# COMECA_TestSCH.net
KiCad netlist of a schematic drawn in Altium Designer
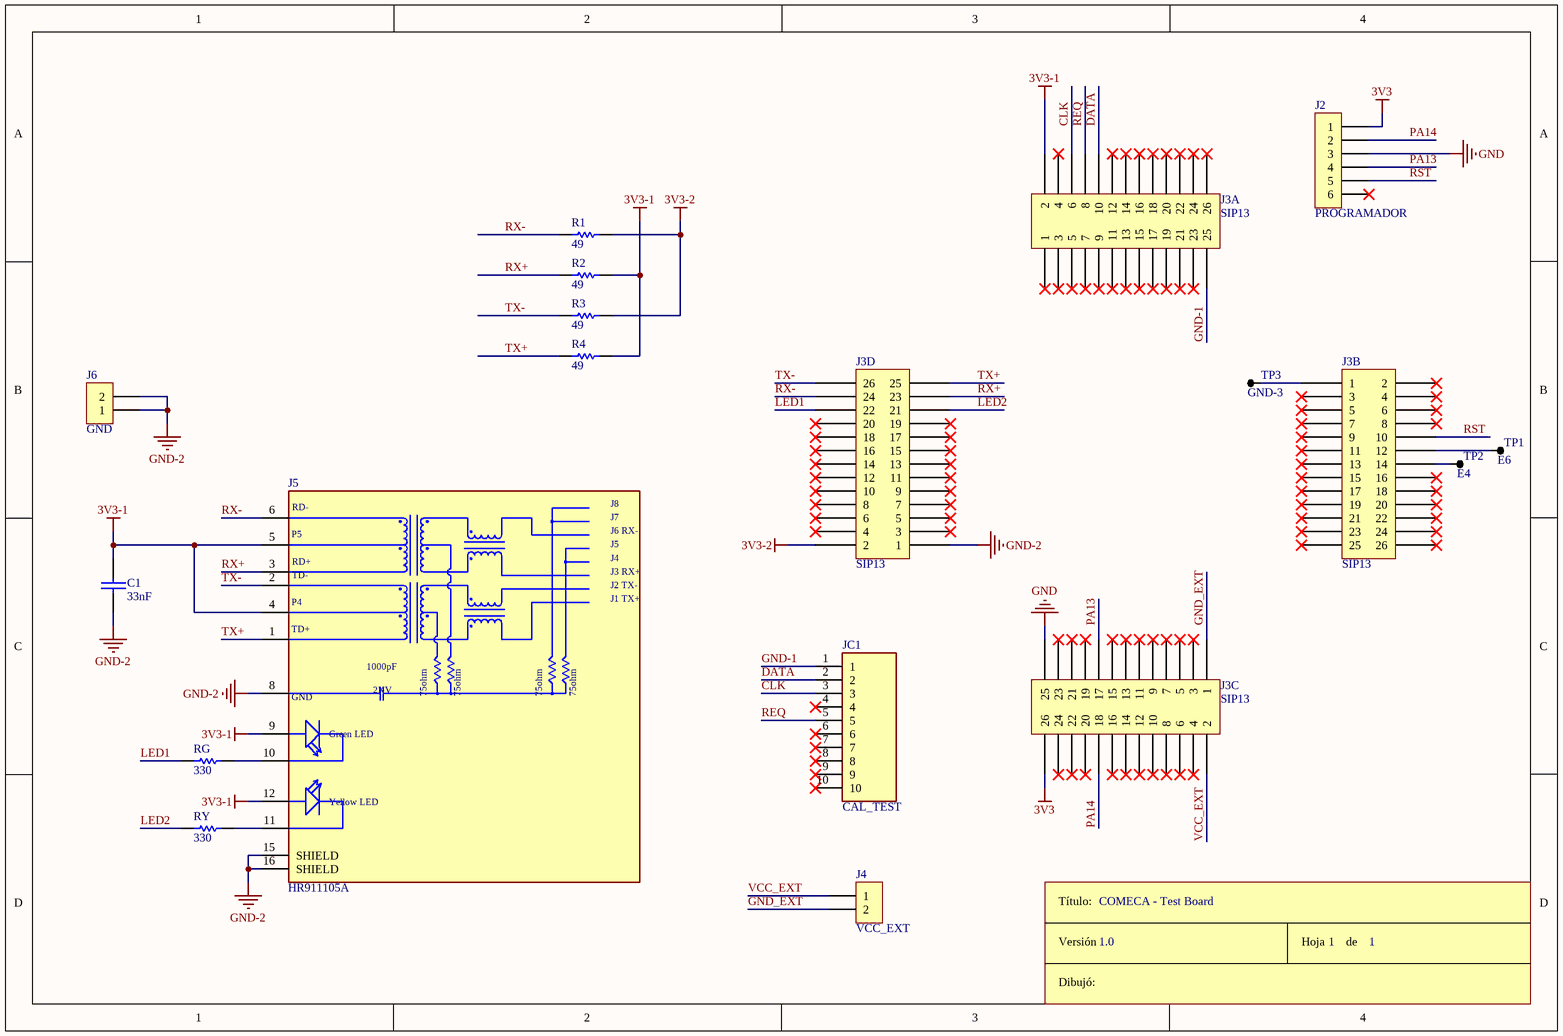
[diagram p0: COMECA_TestSCH.SchDoc]

(export (version "E")
  (design (tool "Eeschema 10.0.6"))
  (components
    (comp (ref "C1") (value "33nF") (footprint "CAP100") (libsource (lib "LIBEBAL") (part "CAP")))
    (comp (ref "J2") (value "PROGRAMADOR") (footprint "SIP6") (libsource (lib "LIBEBAL") (part "CON6")))
    (comp (ref "J3A")
      (value "SIP13")
      (footprint "SIP13*2 - HDR")
      (libsource (lib "AditionalComponents") (part "CON13*2"))
    )
    (comp (ref "J3B") (value "SIP13") (footprint "SIP13*2 - HDR") (libsource (lib "") (part "CON13*2_2")))
    (comp (ref "J3C") (value "SIP13") (footprint "SIP13*2 - HDR") (libsource (lib "") (part "CON13*2_1")))
    (comp (ref "J3D") (value "SIP13") (footprint "SIP13*2 - HDR") (libsource (lib "") (part "CON13*2_3")))
    (comp (ref "J4") (value "VCC_EXT") (footprint "SIP2") (libsource (lib "") (part "CON2_1")))
    (comp (ref "J5")
      (value "HR911105A")
      (footprint "HANRUN_HR911105A")
      (description "HR911105A Ethernet Interface Arduino Platform Evaluation Expansion Board")
      (fields (field (name "MF") "DFRobot"))
      (libsource (lib "HR911105A") (part "HR911105A"))
    )
    (comp (ref "J6") (value "GND") (footprint "SIP2") (libsource (lib "LIBEBAL") (part "CON2")))
    (comp (ref "JC1")
      (value "CAL_TEST")
      (footprint "TE_5104338-1 - 90DEG")
      (description "HEADER; PIN; AMP-LATCH; 10 POS; 2.54 X 2.54; VERTICAL; LOW PROFILE; PCB")
      (fields (field (name "MF") "TE Connectivity") (field (name "MP") "5104338-1"))
      (libsource (lib "HDR10-M") (part "5104338-1"))
    )
    (comp (ref "R1") (value "49") (footprint "RES400") (libsource (lib "LIBEBAL") (part "RES")))
    (comp (ref "R2") (value "49") (footprint "RES400") (libsource (lib "LIBEBAL") (part "RES")))
    (comp (ref "R3") (value "49") (footprint "RES400") (libsource (lib "LIBEBAL") (part "RES")))
    (comp (ref "R4") (value "49") (footprint "RES400") (libsource (lib "LIBEBAL") (part "RES")))
    (comp (ref "RG") (value "330") (footprint "RES400") (libsource (lib "LIBEBAL") (part "RES")))
    (comp (ref "ROT1") (value "Rótulo") (libsource (lib "LIB PIO IX") (part "Rótulo")))
    (comp (ref "RY") (value "330") (footprint "RES400") (libsource (lib "LIBEBAL") (part "RES")))
    (comp (ref "TP1") (value "E6") (footprint "TPTH") (libsource (lib "LIBEBAL") (part "TP")))
    (comp (ref "TP2") (value "E4") (footprint "TPTH") (libsource (lib "LIBEBAL") (part "TP")))
    (comp (ref "TP3") (value "GND-3") (footprint "TPTH") (libsource (lib "LIBEBAL") (part "TP")))
  )
  (nets
    (net (code "1") (name "/CLK") (class "Default")
      (node (ref "J3A") (pin "6") (pinfunction "6_6") (pintype "passive"))
      (node (ref "JC1") (pin "3") (pinfunction "3_3") (pintype "passive"))
    )
    (net (code "2") (name "/DATA") (class "Default")
      (node (ref "J3A") (pin "10") (pinfunction "10_10") (pintype "passive"))
      (node (ref "JC1") (pin "2") (pinfunction "2_2") (pintype "passive"))
    )
    (net (code "3") (name "/GND-1") (class "Default")
      (node (ref "J3A") (pin "25") (pinfunction "25_25") (pintype "passive"))
      (node (ref "JC1") (pin "1") (pinfunction "1_1") (pintype "passive"))
    )
    (net (code "4") (name "/GND_EXT") (class "Default")
      (node (ref "J3C") (pin "1") (pinfunction "1_1") (pintype "passive"))
      (node (ref "J4") (pin "2") (pinfunction "2_2") (pintype "passive"))
    )
    (net (code "5") (name "/LED1") (class "Default")
      (node (ref "J3D") (pin "22") (pinfunction "22_22") (pintype "passive"))
      (node (ref "RG") (pin "1") (pinfunction "1_1") (pintype "passive"))
    )
    (net (code "6") (name "/LED2") (class "Default")
      (node (ref "J3D") (pin "21") (pinfunction "21_21") (pintype "passive"))
      (node (ref "RY") (pin "1") (pinfunction "1_1") (pintype "passive"))
    )
    (net (code "7") (name "/PA13") (class "Default")
      (node (ref "J2") (pin "4") (pinfunction "4_4") (pintype "passive"))
      (node (ref "J3C") (pin "17") (pinfunction "17_17") (pintype "passive"))
    )
    (net (code "8") (name "/PA14") (class "Default")
      (node (ref "J2") (pin "2") (pinfunction "2_2") (pintype "passive"))
      (node (ref "J3C") (pin "18") (pinfunction "18_18") (pintype "passive"))
    )
    (net (code "9") (name "/REQ") (class "Default")
      (node (ref "J3A") (pin "8") (pinfunction "8_8") (pintype "passive"))
      (node (ref "JC1") (pin "5") (pinfunction "5_5") (pintype "passive"))
    )
    (net (code "10") (name "/RST") (class "Default")
      (node (ref "J2") (pin "5") (pinfunction "5_5") (pintype "passive"))
      (node (ref "J3B") (pin "10") (pinfunction "10_10") (pintype "passive"))
    )
    (net (code "11") (name "/RX+") (class "Default")
      (node (ref "J3D") (pin "23") (pinfunction "23_23") (pintype "passive"))
      (node (ref "J5") (pin "3") (pinfunction "RD+_3") (pintype "passive"))
      (node (ref "R2") (pin "1") (pinfunction "1_1") (pintype "passive"))
    )
    (net (code "12") (name "/RX-") (class "Default")
      (node (ref "J3D") (pin "24") (pinfunction "24_24") (pintype "passive"))
      (node (ref "J5") (pin "6") (pinfunction "RD-_6") (pintype "passive"))
      (node (ref "R1") (pin "1") (pinfunction "1_1") (pintype "passive"))
    )
    (net (code "13") (name "/TX+") (class "Default")
      (node (ref "J3D") (pin "25") (pinfunction "25_25") (pintype "passive"))
      (node (ref "J5") (pin "1") (pinfunction "TD+_1") (pintype "passive"))
      (node (ref "R4") (pin "1") (pinfunction "1_1") (pintype "passive"))
    )
    (net (code "14") (name "/TX-") (class "Default")
      (node (ref "J3D") (pin "26") (pinfunction "26_26") (pintype "passive"))
      (node (ref "J5") (pin "2") (pinfunction "TD-_2") (pintype "passive"))
      (node (ref "R3") (pin "1") (pinfunction "1_1") (pintype "passive"))
    )
    (net (code "15") (name "/VCC_EXT") (class "Default")
      (node (ref "J3C") (pin "2") (pinfunction "2_2") (pintype "passive"))
      (node (ref "J4") (pin "1") (pinfunction "1_1") (pintype "passive"))
    )
    (net (code "16") (name "3V3") (class "Default")
      (node (ref "J2") (pin "1") (pinfunction "1_1") (pintype "passive"))
      (node (ref "J3C") (pin "26") (pinfunction "26_26") (pintype "passive"))
    )
    (net (code "17") (name "3V3-1") (class "Default")
      (node (ref "C1") (pin "1") (pinfunction "1_1") (pintype "passive"))
      (node (ref "J3A") (pin "2") (pinfunction "2_2") (pintype "passive"))
      (node (ref "J5") (pin "12") (pinfunction "YA_12") (pintype "passive"))
      (node (ref "J5") (pin "4") (pinfunction "P4_4") (pintype "passive"))
      (node (ref "J5") (pin "5") (pinfunction "P5_5") (pintype "passive"))
      (node (ref "J5") (pin "9") (pinfunction "GA_9") (pintype "passive"))
      (node (ref "R2") (pin "2") (pinfunction "2_2") (pintype "passive"))
      (node (ref "R4") (pin "2") (pinfunction "2_2") (pintype "passive"))
    )
    (net (code "18") (name "3V3-2") (class "Default")
      (node (ref "J3D") (pin "2") (pinfunction "2_2") (pintype "passive"))
      (node (ref "R1") (pin "2") (pinfunction "2_2") (pintype "passive"))
      (node (ref "R3") (pin "2") (pinfunction "2_2") (pintype "passive"))
    )
    (net (code "19") (name "GND") (class "Default")
      (node (ref "J2") (pin "3") (pinfunction "3_3") (pintype "passive"))
      (node (ref "J3C") (pin "25") (pinfunction "25_25") (pintype "passive"))
    )
    (net (code "20") (name "GND-2") (class "Default")
      (node (ref "C1") (pin "2") (pinfunction "2_2") (pintype "passive"))
      (node (ref "J3D") (pin "1") (pinfunction "1_1") (pintype "passive"))
      (node (ref "J5") (pin "15") (pinfunction "SHIELD_15") (pintype "passive"))
      (node (ref "J5") (pin "16") (pinfunction "SHIELD_16") (pintype "passive"))
      (node (ref "J5") (pin "8") (pinfunction "GND_8") (pintype "power_in"))
      (node (ref "J6") (pin "1") (pinfunction "1_1") (pintype "passive"))
      (node (ref "J6") (pin "2") (pinfunction "2_2") (pintype "passive"))
    )
    (net (code "21") (name "Net-(J3B-Pad1)") (class "Default")
      (node (ref "J3B") (pin "1") (pinfunction "1_1") (pintype "passive"))
      (node (ref "TP3") (pin "1") (pinfunction "1_1") (pintype "passive"))
    )
    (net (code "22") (name "Net-(J3B-Pad12)") (class "Default")
      (node (ref "J3B") (pin "12") (pinfunction "12_12") (pintype "passive"))
      (node (ref "TP1") (pin "1") (pinfunction "1_1") (pintype "passive"))
    )
    (net (code "23") (name "Net-(J3B-Pad14)") (class "Default")
      (node (ref "J3B") (pin "14") (pinfunction "14_14") (pintype "passive"))
      (node (ref "TP2") (pin "1") (pinfunction "1_1") (pintype "passive"))
    )
    (net (code "24") (name "Net-(J5-GC)") (class "Default")
      (node (ref "J5") (pin "10") (pinfunction "GC_10") (pintype "passive"))
      (node (ref "RG") (pin "2") (pinfunction "2_2") (pintype "passive"))
    )
    (net (code "25") (name "Net-(J5-YC)") (class "Default")
      (node (ref "J5") (pin "11") (pinfunction "YC_11") (pintype "passive"))
      (node (ref "RY") (pin "2") (pinfunction "2_2") (pintype "passive"))
    )
    (net (code "26") (name "unconnected-(J2-Pad6)") (class "Default")
      (node (ref "J2") (pin "6") (pinfunction "6_6") (pintype "passive+no_connect"))
    )
    (net (code "27") (name "unconnected-(J3A-Pad1)") (class "Default")
      (node (ref "J3A") (pin "1") (pinfunction "1_1") (pintype "passive+no_connect"))
    )
    (net (code "28") (name "unconnected-(J3A-Pad3)") (class "Default")
      (node (ref "J3A") (pin "3") (pinfunction "3_3") (pintype "passive+no_connect"))
    )
    (net (code "29") (name "unconnected-(J3A-Pad4)") (class "Default")
      (node (ref "J3A") (pin "4") (pinfunction "4_4") (pintype "passive+no_connect"))
    )
    (net (code "30") (name "unconnected-(J3A-Pad5)") (class "Default")
      (node (ref "J3A") (pin "5") (pinfunction "5_5") (pintype "passive+no_connect"))
    )
    (net (code "31") (name "unconnected-(J3A-Pad7)") (class "Default")
      (node (ref "J3A") (pin "7") (pinfunction "7_7") (pintype "passive+no_connect"))
    )
    (net (code "32") (name "unconnected-(J3A-Pad9)") (class "Default")
      (node (ref "J3A") (pin "9") (pinfunction "9_9") (pintype "passive+no_connect"))
    )
    (net (code "33") (name "unconnected-(J3A-Pad11)") (class "Default")
      (node (ref "J3A") (pin "11") (pinfunction "11_11") (pintype "passive+no_connect"))
    )
    (net (code "34") (name "unconnected-(J3A-Pad12)") (class "Default")
      (node (ref "J3A") (pin "12") (pinfunction "12_12") (pintype "passive+no_connect"))
    )
    (net (code "35") (name "unconnected-(J3A-Pad13)") (class "Default")
      (node (ref "J3A") (pin "13") (pinfunction "13_13") (pintype "passive+no_connect"))
    )
    (net (code "36") (name "unconnected-(J3A-Pad14)") (class "Default")
      (node (ref "J3A") (pin "14") (pinfunction "14_14") (pintype "passive+no_connect"))
    )
    (net (code "37") (name "unconnected-(J3A-Pad15)") (class "Default")
      (node (ref "J3A") (pin "15") (pinfunction "15_15") (pintype "passive+no_connect"))
    )
    (net (code "38") (name "unconnected-(J3A-Pad16)") (class "Default")
      (node (ref "J3A") (pin "16") (pinfunction "16_16") (pintype "passive+no_connect"))
    )
    (net (code "39") (name "unconnected-(J3A-Pad17)") (class "Default")
      (node (ref "J3A") (pin "17") (pinfunction "17_17") (pintype "passive+no_connect"))
    )
    (net (code "40") (name "unconnected-(J3A-Pad18)") (class "Default")
      (node (ref "J3A") (pin "18") (pinfunction "18_18") (pintype "passive+no_connect"))
    )
    (net (code "41") (name "unconnected-(J3A-Pad19)") (class "Default")
      (node (ref "J3A") (pin "19") (pinfunction "19_19") (pintype "passive+no_connect"))
    )
    (net (code "42") (name "unconnected-(J3A-Pad20)") (class "Default")
      (node (ref "J3A") (pin "20") (pinfunction "20_20") (pintype "passive+no_connect"))
    )
    (net (code "43") (name "unconnected-(J3A-Pad21)") (class "Default")
      (node (ref "J3A") (pin "21") (pinfunction "21_21") (pintype "passive+no_connect"))
    )
    (net (code "44") (name "unconnected-(J3A-Pad22)") (class "Default")
      (node (ref "J3A") (pin "22") (pinfunction "22_22") (pintype "passive+no_connect"))
    )
    (net (code "45") (name "unconnected-(J3A-Pad23)") (class "Default")
      (node (ref "J3A") (pin "23") (pinfunction "23_23") (pintype "passive+no_connect"))
    )
    (net (code "46") (name "unconnected-(J3A-Pad24)") (class "Default")
      (node (ref "J3A") (pin "24") (pinfunction "24_24") (pintype "passive+no_connect"))
    )
    (net (code "47") (name "unconnected-(J3A-Pad26)") (class "Default")
      (node (ref "J3A") (pin "26") (pinfunction "26_26") (pintype "passive+no_connect"))
    )
    (net (code "48") (name "unconnected-(J3B-Pad2)") (class "Default")
      (node (ref "J3B") (pin "2") (pinfunction "2_2") (pintype "passive+no_connect"))
    )
    (net (code "49") (name "unconnected-(J3B-Pad3)") (class "Default")
      (node (ref "J3B") (pin "3") (pinfunction "3_3") (pintype "passive+no_connect"))
    )
    (net (code "50") (name "unconnected-(J3B-Pad4)") (class "Default")
      (node (ref "J3B") (pin "4") (pinfunction "4_4") (pintype "passive+no_connect"))
    )
    (net (code "51") (name "unconnected-(J3B-Pad5)") (class "Default")
      (node (ref "J3B") (pin "5") (pinfunction "5_5") (pintype "passive+no_connect"))
    )
    (net (code "52") (name "unconnected-(J3B-Pad6)") (class "Default")
      (node (ref "J3B") (pin "6") (pinfunction "6_6") (pintype "passive+no_connect"))
    )
    (net (code "53") (name "unconnected-(J3B-Pad7)") (class "Default")
      (node (ref "J3B") (pin "7") (pinfunction "7_7") (pintype "passive+no_connect"))
    )
    (net (code "54") (name "unconnected-(J3B-Pad8)") (class "Default")
      (node (ref "J3B") (pin "8") (pinfunction "8_8") (pintype "passive+no_connect"))
    )
    (net (code "55") (name "unconnected-(J3B-Pad9)") (class "Default")
      (node (ref "J3B") (pin "9") (pinfunction "9_9") (pintype "passive+no_connect"))
    )
    (net (code "56") (name "unconnected-(J3B-Pad11)") (class "Default")
      (node (ref "J3B") (pin "11") (pinfunction "11_11") (pintype "passive+no_connect"))
    )
    (net (code "57") (name "unconnected-(J3B-Pad13)") (class "Default")
      (node (ref "J3B") (pin "13") (pinfunction "13_13") (pintype "passive+no_connect"))
    )
    (net (code "58") (name "unconnected-(J3B-Pad15)") (class "Default")
      (node (ref "J3B") (pin "15") (pinfunction "15_15") (pintype "passive+no_connect"))
    )
    (net (code "59") (name "unconnected-(J3B-Pad16)") (class "Default")
      (node (ref "J3B") (pin "16") (pinfunction "16_16") (pintype "passive+no_connect"))
    )
    (net (code "60") (name "unconnected-(J3B-Pad17)") (class "Default")
      (node (ref "J3B") (pin "17") (pinfunction "17_17") (pintype "passive+no_connect"))
    )
    (net (code "61") (name "unconnected-(J3B-Pad18)") (class "Default")
      (node (ref "J3B") (pin "18") (pinfunction "18_18") (pintype "passive+no_connect"))
    )
    (net (code "62") (name "unconnected-(J3B-Pad19)") (class "Default")
      (node (ref "J3B") (pin "19") (pinfunction "19_19") (pintype "passive+no_connect"))
    )
    (net (code "63") (name "unconnected-(J3B-Pad20)") (class "Default")
      (node (ref "J3B") (pin "20") (pinfunction "20_20") (pintype "passive+no_connect"))
    )
    (net (code "64") (name "unconnected-(J3B-Pad21)") (class "Default")
      (node (ref "J3B") (pin "21") (pinfunction "21_21") (pintype "passive+no_connect"))
    )
    (net (code "65") (name "unconnected-(J3B-Pad22)") (class "Default")
      (node (ref "J3B") (pin "22") (pinfunction "22_22") (pintype "passive+no_connect"))
    )
    (net (code "66") (name "unconnected-(J3B-Pad23)") (class "Default")
      (node (ref "J3B") (pin "23") (pinfunction "23_23") (pintype "passive+no_connect"))
    )
    (net (code "67") (name "unconnected-(J3B-Pad24)") (class "Default")
      (node (ref "J3B") (pin "24") (pinfunction "24_24") (pintype "passive+no_connect"))
    )
    (net (code "68") (name "unconnected-(J3B-Pad25)") (class "Default")
      (node (ref "J3B") (pin "25") (pinfunction "25_25") (pintype "passive+no_connect"))
    )
    (net (code "69") (name "unconnected-(J3B-Pad26)") (class "Default")
      (node (ref "J3B") (pin "26") (pinfunction "26_26") (pintype "passive+no_connect"))
    )
    (net (code "70") (name "unconnected-(J3C-Pad3)") (class "Default")
      (node (ref "J3C") (pin "3") (pinfunction "3_3") (pintype "passive+no_connect"))
    )
    (net (code "71") (name "unconnected-(J3C-Pad4)") (class "Default")
      (node (ref "J3C") (pin "4") (pinfunction "4_4") (pintype "passive+no_connect"))
    )
    (net (code "72") (name "unconnected-(J3C-Pad5)") (class "Default")
      (node (ref "J3C") (pin "5") (pinfunction "5_5") (pintype "passive+no_connect"))
    )
    (net (code "73") (name "unconnected-(J3C-Pad6)") (class "Default")
      (node (ref "J3C") (pin "6") (pinfunction "6_6") (pintype "passive+no_connect"))
    )
    (net (code "74") (name "unconnected-(J3C-Pad7)") (class "Default")
      (node (ref "J3C") (pin "7") (pinfunction "7_7") (pintype "passive+no_connect"))
    )
    (net (code "75") (name "unconnected-(J3C-Pad8)") (class "Default")
      (node (ref "J3C") (pin "8") (pinfunction "8_8") (pintype "passive+no_connect"))
    )
    (net (code "76") (name "unconnected-(J3C-Pad9)") (class "Default")
      (node (ref "J3C") (pin "9") (pinfunction "9_9") (pintype "passive+no_connect"))
    )
    (net (code "77") (name "unconnected-(J3C-Pad10)") (class "Default")
      (node (ref "J3C") (pin "10") (pinfunction "10_10") (pintype "passive+no_connect"))
    )
    (net (code "78") (name "unconnected-(J3C-Pad11)") (class "Default")
      (node (ref "J3C") (pin "11") (pinfunction "11_11") (pintype "passive+no_connect"))
    )
    (net (code "79") (name "unconnected-(J3C-Pad12)") (class "Default")
      (node (ref "J3C") (pin "12") (pinfunction "12_12") (pintype "passive+no_connect"))
    )
    (net (code "80") (name "unconnected-(J3C-Pad13)") (class "Default")
      (node (ref "J3C") (pin "13") (pinfunction "13_13") (pintype "passive+no_connect"))
    )
    (net (code "81") (name "unconnected-(J3C-Pad14)") (class "Default")
      (node (ref "J3C") (pin "14") (pinfunction "14_14") (pintype "passive+no_connect"))
    )
    (net (code "82") (name "unconnected-(J3C-Pad15)") (class "Default")
      (node (ref "J3C") (pin "15") (pinfunction "15_15") (pintype "passive+no_connect"))
    )
    (net (code "83") (name "unconnected-(J3C-Pad16)") (class "Default")
      (node (ref "J3C") (pin "16") (pinfunction "16_16") (pintype "passive+no_connect"))
    )
    (net (code "84") (name "unconnected-(J3C-Pad19)") (class "Default")
      (node (ref "J3C") (pin "19") (pinfunction "19_19") (pintype "passive+no_connect"))
    )
    (net (code "85") (name "unconnected-(J3C-Pad20)") (class "Default")
      (node (ref "J3C") (pin "20") (pinfunction "20_20") (pintype "passive+no_connect"))
    )
    (net (code "86") (name "unconnected-(J3C-Pad21)") (class "Default")
      (node (ref "J3C") (pin "21") (pinfunction "21_21") (pintype "passive+no_connect"))
    )
    (net (code "87") (name "unconnected-(J3C-Pad22)") (class "Default")
      (node (ref "J3C") (pin "22") (pinfunction "22_22") (pintype "passive+no_connect"))
    )
    (net (code "88") (name "unconnected-(J3C-Pad23)") (class "Default")
      (node (ref "J3C") (pin "23") (pinfunction "23_23") (pintype "passive+no_connect"))
    )
    (net (code "89") (name "unconnected-(J3C-Pad24)") (class "Default")
      (node (ref "J3C") (pin "24") (pinfunction "24_24") (pintype "passive+no_connect"))
    )
    (net (code "90") (name "unconnected-(J3D-Pad3)") (class "Default")
      (node (ref "J3D") (pin "3") (pinfunction "3_3") (pintype "passive+no_connect"))
    )
    (net (code "91") (name "unconnected-(J3D-Pad4)") (class "Default")
      (node (ref "J3D") (pin "4") (pinfunction "4_4") (pintype "passive+no_connect"))
    )
    (net (code "92") (name "unconnected-(J3D-Pad5)") (class "Default")
      (node (ref "J3D") (pin "5") (pinfunction "5_5") (pintype "passive+no_connect"))
    )
    (net (code "93") (name "unconnected-(J3D-Pad6)") (class "Default")
      (node (ref "J3D") (pin "6") (pinfunction "6_6") (pintype "passive+no_connect"))
    )
    (net (code "94") (name "unconnected-(J3D-Pad7)") (class "Default")
      (node (ref "J3D") (pin "7") (pinfunction "7_7") (pintype "passive+no_connect"))
    )
    (net (code "95") (name "unconnected-(J3D-Pad8)") (class "Default")
      (node (ref "J3D") (pin "8") (pinfunction "8_8") (pintype "passive+no_connect"))
    )
    (net (code "96") (name "unconnected-(J3D-Pad9)") (class "Default")
      (node (ref "J3D") (pin "9") (pinfunction "9_9") (pintype "passive+no_connect"))
    )
    (net (code "97") (name "unconnected-(J3D-Pad10)") (class "Default")
      (node (ref "J3D") (pin "10") (pinfunction "10_10") (pintype "passive+no_connect"))
    )
    (net (code "98") (name "unconnected-(J3D-Pad11)") (class "Default")
      (node (ref "J3D") (pin "11") (pinfunction "11_11") (pintype "passive+no_connect"))
    )
    (net (code "99") (name "unconnected-(J3D-Pad12)") (class "Default")
      (node (ref "J3D") (pin "12") (pinfunction "12_12") (pintype "passive+no_connect"))
    )
    (net (code "100") (name "unconnected-(J3D-Pad13)") (class "Default")
      (node (ref "J3D") (pin "13") (pinfunction "13_13") (pintype "passive+no_connect"))
    )
    (net (code "101") (name "unconnected-(J3D-Pad14)") (class "Default")
      (node (ref "J3D") (pin "14") (pinfunction "14_14") (pintype "passive+no_connect"))
    )
    (net (code "102") (name "unconnected-(J3D-Pad15)") (class "Default")
      (node (ref "J3D") (pin "15") (pinfunction "15_15") (pintype "passive+no_connect"))
    )
    (net (code "103") (name "unconnected-(J3D-Pad16)") (class "Default")
      (node (ref "J3D") (pin "16") (pinfunction "16_16") (pintype "passive+no_connect"))
    )
    (net (code "104") (name "unconnected-(J3D-Pad17)") (class "Default")
      (node (ref "J3D") (pin "17") (pinfunction "17_17") (pintype "passive+no_connect"))
    )
    (net (code "105") (name "unconnected-(J3D-Pad18)") (class "Default")
      (node (ref "J3D") (pin "18") (pinfunction "18_18") (pintype "passive+no_connect"))
    )
    (net (code "106") (name "unconnected-(J3D-Pad19)") (class "Default")
      (node (ref "J3D") (pin "19") (pinfunction "19_19") (pintype "passive+no_connect"))
    )
    (net (code "107") (name "unconnected-(J3D-Pad20)") (class "Default")
      (node (ref "J3D") (pin "20") (pinfunction "20_20") (pintype "passive+no_connect"))
    )
    (net (code "108") (name "unconnected-(JC1-Pad4)") (class "Default")
      (node (ref "JC1") (pin "4") (pinfunction "4_4") (pintype "passive+no_connect"))
    )
    (net (code "109") (name "unconnected-(JC1-Pad6)") (class "Default")
      (node (ref "JC1") (pin "6") (pinfunction "6_6") (pintype "passive+no_connect"))
    )
    (net (code "110") (name "unconnected-(JC1-Pad7)") (class "Default")
      (node (ref "JC1") (pin "7") (pinfunction "7_7") (pintype "passive+no_connect"))
    )
    (net (code "111") (name "unconnected-(JC1-Pad8)") (class "Default")
      (node (ref "JC1") (pin "8") (pinfunction "8_8") (pintype "passive+no_connect"))
    )
    (net (code "112") (name "unconnected-(JC1-Pad9)") (class "Default")
      (node (ref "JC1") (pin "9") (pinfunction "9_9") (pintype "passive+no_connect"))
    )
    (net (code "113") (name "unconnected-(JC1-Pad10)") (class "Default")
      (node (ref "JC1") (pin "10") (pinfunction "10_10") (pintype "passive+no_connect"))
    )
  )
)
